# mcp2200.net
KiCad netlist of a schematic drawn in EAGLE
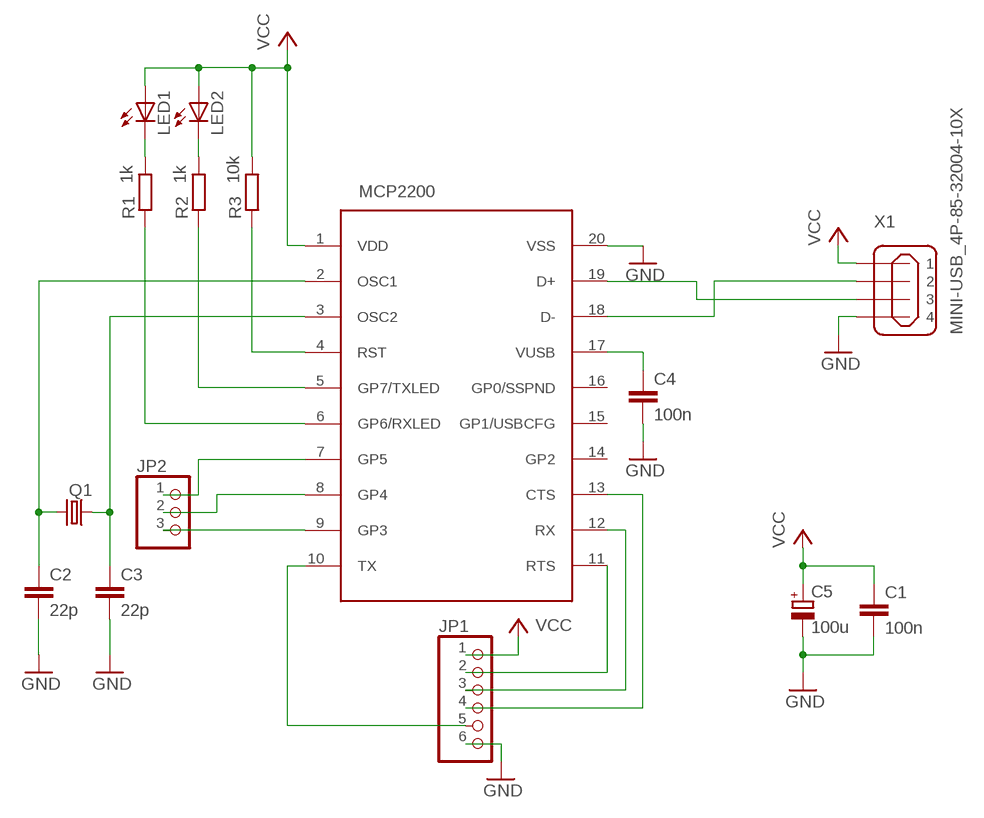
[diagram p0: schematic, sheet 1]

(export (version "E")
  (design (tool "Eeschema 10.0.6"))
  (components
    (comp (ref "C1")
      (value "100n")
      (footprint "eagle-import:C025-025X050")
      (libsource (lib "eagle-import") (part "C-EU025-025X050"))
    )
    (comp (ref "C2")
      (value "22p")
      (footprint "eagle-import:C025-025X050")
      (libsource (lib "eagle-import") (part "C-EU025-025X050"))
    )
    (comp (ref "C3")
      (value "22p")
      (footprint "eagle-import:C025-025X050")
      (libsource (lib "eagle-import") (part "C-EU025-025X050"))
    )
    (comp (ref "C4")
      (value "100n")
      (footprint "eagle-import:C025-025X050")
      (libsource (lib "eagle-import") (part "C-EU025-025X050"))
    )
    (comp (ref "C5")
      (value "100u")
      (footprint "eagle-import:E3,5-8")
      (libsource (lib "eagle-import") (part "CPOL-EUE3.5-8"))
    )
    (comp (ref "JP1")
      (value "PINHD-1X6")
      (footprint "eagle-import:1X06")
      (libsource (lib "eagle-import") (part "PINHD-1X6"))
    )
    (comp (ref "JP2")
      (value "PINHD-1X3")
      (footprint "eagle-import:1X03")
      (libsource (lib "eagle-import") (part "PINHD-1X3"))
    )
    (comp (ref "LED1")
      (value "LED3MM")
      (footprint "eagle-import:LED3MM")
      (libsource (lib "eagle-import") (part "LED3MM"))
    )
    (comp (ref "LED2")
      (value "LED3MM")
      (footprint "eagle-import:LED3MM")
      (libsource (lib "eagle-import") (part "LED3MM"))
    )
    (comp (ref "MCP2200")
      (value "MCP2200")
      (footprint "eagle-import:SOIC127P1032X265-20")
      (libsource (lib "eagle-import") (part "MCP2200"))
    )
    (comp (ref "Q1")
      (value "CRYSTALHC49S")
      (footprint "eagle-import:HC49_S")
      (libsource (lib "eagle-import") (part "CRYSTALHC49S"))
    )
    (comp (ref "R1")
      (value "1k")
      (footprint "eagle-import:R1206")
      (libsource (lib "eagle-import") (part "R-EU_R1206"))
    )
    (comp (ref "R2")
      (value "1k")
      (footprint "eagle-import:R1206")
      (libsource (lib "eagle-import") (part "R-EU_R1206"))
    )
    (comp (ref "R3")
      (value "10k")
      (footprint "eagle-import:R1206")
      (libsource (lib "eagle-import") (part "R-EU_R1206"))
    )
    (comp (ref "X1")
      (value "MINI-USB_4P-85-32004-10X")
      (footprint "eagle-import:85-32004-10X")
      (libsource (lib "eagle-import") (part "MINI-USB_4P-85-32004-10X"))
    )
  )
  (nets
    (net (code "1") (name "GND") (class "Default")
      (node (ref "C1") (pin "2") (pinfunction "2_2") (pintype "passive"))
      (node (ref "C2") (pin "2") (pinfunction "2_2") (pintype "passive"))
      (node (ref "C3") (pin "2") (pinfunction "2_2") (pintype "passive"))
      (node (ref "C4") (pin "2") (pinfunction "2_2") (pintype "passive"))
      (node (ref "C5") (pin "-") (pinfunction "-_-") (pintype "passive"))
      (node (ref "JP1") (pin "6") (pinfunction "6_6") (pintype "passive"))
      (node (ref "MCP2200") (pin "20") (pinfunction "VSS_20") (pintype "bidirectional"))
      (node (ref "X1") (pin "4") (pinfunction "4_4") (pintype "passive"))
    )
    (net (code "2") (name "Net-(LED1-C)") (class "Default")
      (node (ref "LED1") (pin "K") (pinfunction "C_K") (pintype "passive"))
      (node (ref "R1") (pin "2") (pinfunction "2_2") (pintype "passive"))
    )
    (net (code "3") (name "Net-(LED2-C)") (class "Default")
      (node (ref "LED2") (pin "K") (pinfunction "C_K") (pintype "passive"))
      (node (ref "R2") (pin "2") (pinfunction "2_2") (pintype "passive"))
    )
    (net (code "4") (name "Net-(MCP2200-CTS)") (class "Default")
      (node (ref "JP1") (pin "4") (pinfunction "4_4") (pintype "passive"))
      (node (ref "MCP2200") (pin "13") (pinfunction "CTS_13") (pintype "bidirectional"))
    )
    (net (code "5") (name "Net-(MCP2200-D+)") (class "Default")
      (node (ref "MCP2200") (pin "19") (pinfunction "D+_19") (pintype "bidirectional"))
      (node (ref "X1") (pin "3") (pinfunction "3_3") (pintype "passive"))
    )
    (net (code "6") (name "Net-(MCP2200-D-)") (class "Default")
      (node (ref "MCP2200") (pin "18") (pinfunction "D-_18") (pintype "bidirectional"))
      (node (ref "X1") (pin "2") (pinfunction "2_2") (pintype "passive"))
    )
    (net (code "7") (name "Net-(MCP2200-GP3)") (class "Default")
      (node (ref "JP2") (pin "3") (pinfunction "3_3") (pintype "passive"))
      (node (ref "MCP2200") (pin "9") (pinfunction "GP3_9") (pintype "bidirectional"))
    )
    (net (code "8") (name "Net-(MCP2200-GP4)") (class "Default")
      (node (ref "JP2") (pin "2") (pinfunction "2_2") (pintype "passive"))
      (node (ref "MCP2200") (pin "8") (pinfunction "GP4_8") (pintype "bidirectional"))
    )
    (net (code "9") (name "Net-(MCP2200-GP5)") (class "Default")
      (node (ref "JP2") (pin "1") (pinfunction "1_1") (pintype "passive"))
      (node (ref "MCP2200") (pin "7") (pinfunction "GP5_7") (pintype "bidirectional"))
    )
    (net (code "10") (name "Net-(MCP2200-GP6{slash}RXLED)") (class "Default")
      (node (ref "MCP2200") (pin "6") (pinfunction "GP6/RXLED_6") (pintype "bidirectional"))
      (node (ref "R1") (pin "1") (pinfunction "1_1") (pintype "passive"))
    )
    (net (code "11") (name "Net-(MCP2200-GP7{slash}TXLED)") (class "Default")
      (node (ref "MCP2200") (pin "5") (pinfunction "GP7/TXLED_5") (pintype "bidirectional"))
      (node (ref "R2") (pin "1") (pinfunction "1_1") (pintype "passive"))
    )
    (net (code "12") (name "Net-(MCP2200-OSC1)") (class "Default")
      (node (ref "C2") (pin "1") (pinfunction "1_1") (pintype "passive"))
      (node (ref "MCP2200") (pin "2") (pinfunction "OSC1_2") (pintype "bidirectional"))
      (node (ref "Q1") (pin "2") (pinfunction "2_2") (pintype "passive"))
    )
    (net (code "13") (name "Net-(MCP2200-OSC2)") (class "Default")
      (node (ref "C3") (pin "1") (pinfunction "1_1") (pintype "passive"))
      (node (ref "MCP2200") (pin "3") (pinfunction "OSC2_3") (pintype "bidirectional"))
      (node (ref "Q1") (pin "1") (pinfunction "1_1") (pintype "passive"))
    )
    (net (code "14") (name "Net-(MCP2200-RST)") (class "Default")
      (node (ref "MCP2200") (pin "4") (pinfunction "RST_4") (pintype "bidirectional"))
      (node (ref "R3") (pin "1") (pinfunction "1_1") (pintype "passive"))
    )
    (net (code "15") (name "Net-(MCP2200-RTS)") (class "Default")
      (node (ref "JP1") (pin "2") (pinfunction "2_2") (pintype "passive"))
      (node (ref "MCP2200") (pin "11") (pinfunction "RTS_11") (pintype "bidirectional"))
    )
    (net (code "16") (name "Net-(MCP2200-RX)") (class "Default")
      (node (ref "JP1") (pin "3") (pinfunction "3_3") (pintype "passive"))
      (node (ref "MCP2200") (pin "12") (pinfunction "RX_12") (pintype "bidirectional"))
    )
    (net (code "17") (name "Net-(MCP2200-TX)") (class "Default")
      (node (ref "JP1") (pin "5") (pinfunction "5_5") (pintype "passive"))
      (node (ref "MCP2200") (pin "10") (pinfunction "TX_10") (pintype "bidirectional"))
    )
    (net (code "18") (name "Net-(MCP2200-VUSB)") (class "Default")
      (node (ref "C4") (pin "1") (pinfunction "1_1") (pintype "passive"))
      (node (ref "MCP2200") (pin "17") (pinfunction "VUSB_17") (pintype "bidirectional"))
    )
    (net (code "19") (name "VCC") (class "Default")
      (node (ref "C1") (pin "1") (pinfunction "1_1") (pintype "passive"))
      (node (ref "C5") (pin "+") (pinfunction "+_+") (pintype "passive"))
      (node (ref "JP1") (pin "1") (pinfunction "1_1") (pintype "passive"))
      (node (ref "LED1") (pin "A") (pinfunction "A_A") (pintype "passive"))
      (node (ref "LED2") (pin "A") (pinfunction "A_A") (pintype "passive"))
      (node (ref "MCP2200") (pin "1") (pinfunction "VDD_1") (pintype "bidirectional"))
      (node (ref "R3") (pin "2") (pinfunction "2_2") (pintype "passive"))
      (node (ref "X1") (pin "1") (pinfunction "1_1") (pintype "passive"))
    )
    (net (code "20") (name "unconnected-(MCP2200-GP0{slash}SSPND-Pad16)") (class "Default")
      (node (ref "MCP2200") (pin "16") (pinfunction "GP0/SSPND_16") (pintype "bidirectional"))
    )
    (net (code "21") (name "unconnected-(MCP2200-GP1{slash}USBCFG-Pad15)") (class "Default")
      (node (ref "MCP2200") (pin "15") (pinfunction "GP1/USBCFG_15") (pintype "bidirectional"))
    )
    (net (code "22") (name "unconnected-(MCP2200-GP2-Pad14)") (class "Default")
      (node (ref "MCP2200") (pin "14") (pinfunction "GP2_14") (pintype "bidirectional"))
    )
  )
)
